# MPU9250.net
KiCad netlist of a schematic drawn in EAGLE
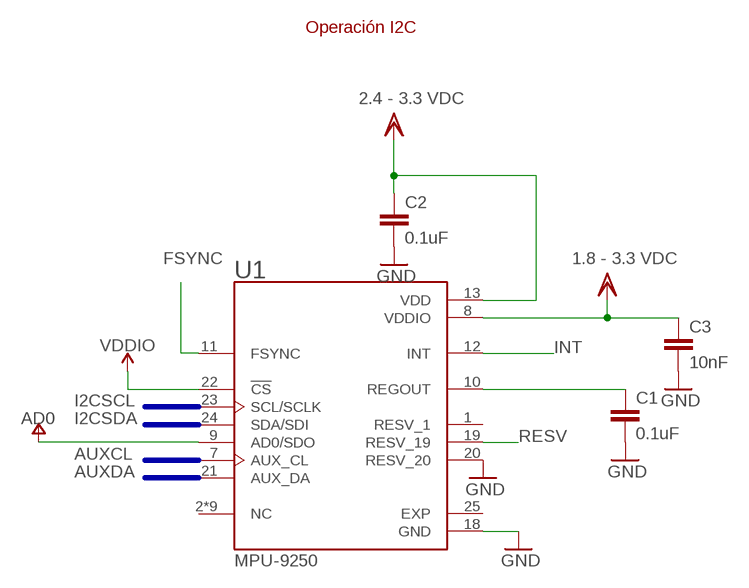
[diagram p0: schematic, sheet 1]

(export (version "E")
  (design (tool "Eeschema 10.0.6"))
  (components
    (comp (ref "C1")
      (value "0.1uF")
      (footprint "eagle-import:1206")
      (libsource (lib "eagle-import") (part "CAP-1206"))
    )
    (comp (ref "C2")
      (value "0.1uF")
      (footprint "eagle-import:1206")
      (libsource (lib "eagle-import") (part "CAP-1206"))
    )
    (comp (ref "C3")
      (value "10nF")
      (footprint "eagle-import:1206")
      (libsource (lib "eagle-import") (part "CAP-1206"))
    )
    (comp (ref "U1")
      (value "MPU-9250")
      (footprint "eagle-import:QFN40P300X300X105-25N")
      (fields (field (name "MF") "TDK InvenSense"))
      (libsource (lib "eagle-import") (part "MPU-9250"))
    )
  )
  (nets
    (net (code "5") (name "/FSYNC") (class "Default")
      (node (ref "U1") (pin "11") (pinfunction "FSYNC_11") (pintype "input"))
    )
    (net (code "6") (name "/INT") (class "Default")
      (node (ref "U1") (pin "12") (pinfunction "INT_12") (pintype "output"))
    )
    (net (code "8") (name "/RESV") (class "Default")
      (node (ref "U1") (pin "19") (pinfunction "RESV_19_19") (pintype "no_connect"))
    )
    (net (code "9") (name "/RESV_1") (class "Default")
      (node (ref "U1") (pin "1") (pinfunction "RESV_1_1") (pintype "power_in"))
    )
    (net (code "10") (name "/{AUXCL}") (class "Default")
      (node (ref "U1") (pin "7") (pinfunction "AUX_CL_7") (pintype "input"))
    )
    (net (code "11") (name "/{AUXDA}") (class "Default")
      (node (ref "U1") (pin "21") (pinfunction "AUX_DA_21") (pintype "input"))
    )
    (net (code "12") (name "/{I2CSCL}") (class "Default")
      (node (ref "U1") (pin "23") (pinfunction "SCL/SCLK_23") (pintype "input"))
    )
    (net (code "13") (name "/{I2CSDA}") (class "Default")
      (node (ref "U1") (pin "24") (pinfunction "SDA/SDI_24") (pintype "bidirectional"))
    )
    (net (code "14") (name "1.8 - 3.3 VDC") (class "Default")
      (node (ref "C2") (pin "1") (pinfunction "1_1") (pintype "passive"))
      (node (ref "C3") (pin "1") (pinfunction "1_1") (pintype "passive"))
      (node (ref "U1") (pin "13") (pinfunction "VDD_13") (pintype "power_in"))
      (node (ref "U1") (pin "8") (pinfunction "VDDIO_8") (pintype "power_in"))
    )
    (net (code "15") (name "AD0") (class "Default")
      (node (ref "U1") (pin "9") (pinfunction "AD0/SDO_9") (pintype "output"))
    )
    (net (code "16") (name "GND") (class "Default")
      (node (ref "C1") (pin "2") (pinfunction "2_2") (pintype "passive"))
      (node (ref "C2") (pin "2") (pinfunction "2_2") (pintype "passive"))
      (node (ref "C3") (pin "2") (pinfunction "2_2") (pintype "passive"))
      (node (ref "U1") (pin "18") (pinfunction "GND_18") (pintype "power_in"))
      (node (ref "U1") (pin "20") (pinfunction "RESV_20_20") (pintype "power_in"))
    )
    (net (code "17") (name "Net-(U1-REGOUT)") (class "Default")
      (node (ref "C1") (pin "1") (pinfunction "1_1") (pintype "passive"))
      (node (ref "U1") (pin "10") (pinfunction "REGOUT_10") (pintype "output"))
    )
    (net (code "18") (name "VDDIO") (class "Default")
      (node (ref "U1") (pin "22") (pinfunction "~{CS}_22") (pintype "input"))
    )
    (net (code "19") (name "unconnected-(U1-EXP-Pad25)") (class "Default")
      (node (ref "U1") (pin "25") (pinfunction "EXP_25") (pintype "passive"))
    )
    (net (code "20") (name "unconnected-(U1-NC-Pad2)") (class "Default")
      (node (ref "U1") (pin "2") (pinfunction "NC_2") (pintype "no_connect"))
    )
    (net (code "21") (name "unconnected-(U1-NC-Pad3)") (class "Default")
      (node (ref "U1") (pin "3") (pinfunction "NC_3") (pintype "no_connect"))
    )
    (net (code "22") (name "unconnected-(U1-NC-Pad4)") (class "Default")
      (node (ref "U1") (pin "4") (pinfunction "NC_4") (pintype "no_connect"))
    )
    (net (code "23") (name "unconnected-(U1-NC-Pad5)") (class "Default")
      (node (ref "U1") (pin "5") (pinfunction "NC_5") (pintype "no_connect"))
    )
    (net (code "24") (name "unconnected-(U1-NC-Pad6)") (class "Default")
      (node (ref "U1") (pin "6") (pinfunction "NC_6") (pintype "no_connect"))
    )
    (net (code "25") (name "unconnected-(U1-NC-Pad14)") (class "Default")
      (node (ref "U1") (pin "14") (pinfunction "NC_14") (pintype "no_connect"))
    )
    (net (code "26") (name "unconnected-(U1-NC-Pad15)") (class "Default")
      (node (ref "U1") (pin "15") (pinfunction "NC_15") (pintype "no_connect"))
    )
    (net (code "27") (name "unconnected-(U1-NC-Pad16)") (class "Default")
      (node (ref "U1") (pin "16") (pinfunction "NC_16") (pintype "no_connect"))
    )
    (net (code "28") (name "unconnected-(U1-NC-Pad17)") (class "Default")
      (node (ref "U1") (pin "17") (pinfunction "NC_17") (pintype "no_connect"))
    )
  )
)
